# Sheet2.net
KiCad netlist of a schematic drawn in Altium Designer
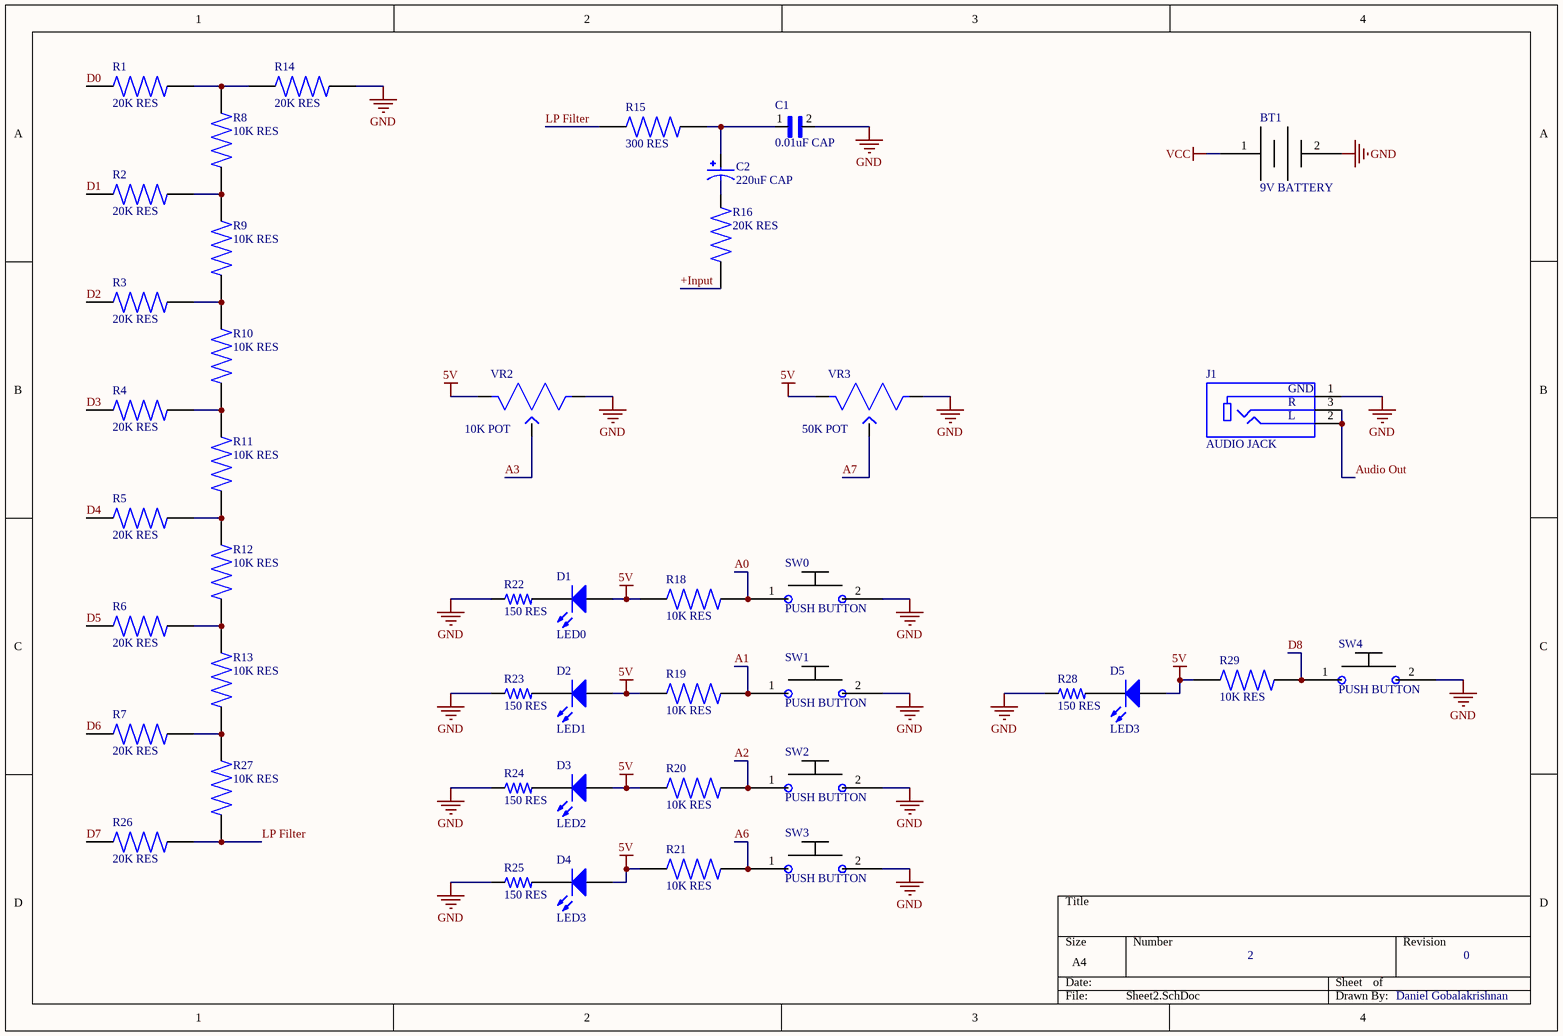
[diagram p0: Sheet2.SchDoc]

(export (version "E")
  (design (tool "Eeschema 10.0.6"))
  (components
    (comp (ref "BT1")
      (value "9V BATTERY")
      (footprint "9V Battery")
      (libsource (lib "Library") (part "9V BATTERY"))
    )
    (comp (ref "C1")
      (value "0.01uF CAP")
      (footprint "10uF CAP")
      (description "Lead Capacitor E(JIS) with Capacitance: 1000pF and Rated Voltage: 400Vac(r.m.s.)")
      (fields (field (name "DIGI-KEY_PART_NUMBER") "490-16237-1-ND") (field (name "MP") "DE2E3SA102MN3AY02F"))
      (libsource (lib "Library") (part "0.01uF CAP"))
    )
    (comp (ref "C2")
      (value "220uF CAP")
      (footprint "220uF CAP")
      (description "33ÂµF 250V Aluminum Electrolytic Capacitors Radial, Can 5000 Hrs @ 105Â°C")
      (fields (field (name "MP") "UPM2E330MHD1TN") (field (name "MF") "Nichicon"))
      (libsource (lib "Library") (part "220uF CAP"))
    )
    (comp (ref "D1")
      (value "LED0")
      (footprint "LED-1")
      (description "Typical RED GaAs LED")
      (fields (field (name "PUBLISHER") "Altium Limited"))
      (libsource (lib "Miscellaneous Devices") (part "LED1"))
    )
    (comp (ref "D2")
      (value "LED1")
      (footprint "LED-1")
      (description "Typical RED GaAs LED")
      (fields (field (name "PUBLISHER") "Altium Limited"))
      (libsource (lib "Miscellaneous Devices") (part "LED1"))
    )
    (comp (ref "D3")
      (value "LED2")
      (footprint "LED-1")
      (description "Typical RED GaAs LED")
      (fields (field (name "PUBLISHER") "Altium Limited"))
      (libsource (lib "Miscellaneous Devices") (part "LED1"))
    )
    (comp (ref "D4")
      (value "LED3")
      (footprint "LED-1")
      (description "Typical RED GaAs LED")
      (fields (field (name "PUBLISHER") "Altium Limited"))
      (libsource (lib "Miscellaneous Devices") (part "LED1"))
    )
    (comp (ref "D5")
      (value "LED3")
      (footprint "LED-1")
      (description "Typical RED GaAs LED")
      (fields (field (name "PUBLISHER") "Altium Limited"))
      (libsource (lib "Miscellaneous Devices") (part "LED1"))
    )
    (comp (ref "J1")
      (value "AUDIO JACK")
      (footprint "AUDIO JACK")
      (description "3.5 mm, Stereo, Right Angle, Through Hole, Audio Jack Connector")
      (fields (field (name "MF") "CUI Devices") (field (name "MP") "SJ1-3533N"))
      (libsource (lib "Library") (part "AUDIO JACK"))
    )
    (comp (ref "R1")
      (value "20K RES")
      (footprint "20K RES")
      (fields (field (name "MP") "RMCF1206JT20K0"))
      (libsource (lib "Library") (part "20K RES"))
    )
    (comp (ref "R2")
      (value "20K RES")
      (footprint "20K RES")
      (fields (field (name "MP") "RMCF1206JT20K0"))
      (libsource (lib "Library") (part "20K RES"))
    )
    (comp (ref "R3")
      (value "20K RES")
      (footprint "20K RES")
      (fields (field (name "MP") "RMCF1206JT20K0"))
      (libsource (lib "Library") (part "20K RES"))
    )
    (comp (ref "R4")
      (value "20K RES")
      (footprint "20K RES")
      (fields (field (name "MP") "RMCF1206JT20K0"))
      (libsource (lib "Library") (part "20K RES"))
    )
    (comp (ref "R5")
      (value "20K RES")
      (footprint "20K RES")
      (fields (field (name "MP") "RMCF1206JT20K0"))
      (libsource (lib "Library") (part "20K RES"))
    )
    (comp (ref "R6")
      (value "20K RES")
      (footprint "20K RES")
      (fields (field (name "MP") "RMCF1206JT20K0"))
      (libsource (lib "Library") (part "20K RES"))
    )
    (comp (ref "R7")
      (value "20K RES")
      (footprint "20K RES")
      (fields (field (name "MP") "RMCF1206JT20K0"))
      (libsource (lib "Library") (part "20K RES"))
    )
    (comp (ref "R8")
      (value "10K RES")
      (footprint "10K RES")
      (description "10 kOhms Â±1% 0.25W, 1/4W Chip Resistor 1206 (3216 Metric) Automotive AEC-Q200 Thick Film")
      (fields (field (name "MP") "RMCF1206FT10K0") (field (name "MF") "Stackpole Electronics Inc"))
      (libsource (lib "Library") (part "10K RES"))
    )
    (comp (ref "R9")
      (value "10K RES")
      (footprint "10K RES")
      (description "10 kOhms Â±1% 0.25W, 1/4W Chip Resistor 1206 (3216 Metric) Automotive AEC-Q200 Thick Film")
      (fields (field (name "MP") "RMCF1206FT10K0") (field (name "MF") "Stackpole Electronics Inc"))
      (libsource (lib "Library") (part "10K RES"))
    )
    (comp (ref "R10")
      (value "10K RES")
      (footprint "10K RES")
      (description "10 kOhms Â±1% 0.25W, 1/4W Chip Resistor 1206 (3216 Metric) Automotive AEC-Q200 Thick Film")
      (fields (field (name "MP") "RMCF1206FT10K0") (field (name "MF") "Stackpole Electronics Inc"))
      (libsource (lib "Library") (part "10K RES"))
    )
    (comp (ref "R11")
      (value "10K RES")
      (footprint "10K RES")
      (description "10 kOhms Â±1% 0.25W, 1/4W Chip Resistor 1206 (3216 Metric) Automotive AEC-Q200 Thick Film")
      (fields (field (name "MP") "RMCF1206FT10K0") (field (name "MF") "Stackpole Electronics Inc"))
      (libsource (lib "Library") (part "10K RES"))
    )
    (comp (ref "R12")
      (value "10K RES")
      (footprint "10K RES")
      (description "10 kOhms Â±1% 0.25W, 1/4W Chip Resistor 1206 (3216 Metric) Automotive AEC-Q200 Thick Film")
      (fields (field (name "MP") "RMCF1206FT10K0") (field (name "MF") "Stackpole Electronics Inc"))
      (libsource (lib "Library") (part "10K RES"))
    )
    (comp (ref "R13")
      (value "10K RES")
      (footprint "10K RES")
      (description "10 kOhms Â±1% 0.25W, 1/4W Chip Resistor 1206 (3216 Metric) Automotive AEC-Q200 Thick Film")
      (fields (field (name "MP") "RMCF1206FT10K0") (field (name "MF") "Stackpole Electronics Inc"))
      (libsource (lib "Library") (part "10K RES"))
    )
    (comp (ref "R14")
      (value "20K RES")
      (footprint "20K RES")
      (fields (field (name "MP") "RMCF1206JT20K0"))
      (libsource (lib "Library") (part "20K RES"))
    )
    (comp (ref "R15")
      (value "300 RES")
      (footprint "300 RES")
      (description "CRCW Series 1206 0.25 W 300 Ohm Â±5 % Â±200 ppm/K SMT Thick Film Chip Resistor")
      (fields (field (name "MP") "CRCW1206300RJNEA"))
      (libsource (lib "Library") (part "300 RES"))
    )
    (comp (ref "R16")
      (value "20K RES")
      (footprint "20K RES")
      (fields (field (name "MP") "RMCF1206JT20K0"))
      (libsource (lib "Library") (part "20K RES"))
    )
    (comp (ref "R18")
      (value "10K RES")
      (footprint "10K RES")
      (description "10 kOhms Â±1% 0.25W, 1/4W Chip Resistor 1206 (3216 Metric) Automotive AEC-Q200 Thick Film")
      (fields (field (name "MP") "RMCF1206FT10K0") (field (name "MF") "Stackpole Electronics Inc"))
      (libsource (lib "Library") (part "10K RES"))
    )
    (comp (ref "R19")
      (value "10K RES")
      (footprint "10K RES")
      (description "10 kOhms Â±1% 0.25W, 1/4W Chip Resistor 1206 (3216 Metric) Automotive AEC-Q200 Thick Film")
      (fields (field (name "MP") "RMCF1206FT10K0") (field (name "MF") "Stackpole Electronics Inc"))
      (libsource (lib "Library") (part "10K RES"))
    )
    (comp (ref "R20")
      (value "10K RES")
      (footprint "10K RES")
      (description "10 kOhms Â±1% 0.25W, 1/4W Chip Resistor 1206 (3216 Metric) Automotive AEC-Q200 Thick Film")
      (fields (field (name "MP") "RMCF1206FT10K0") (field (name "MF") "Stackpole Electronics Inc"))
      (libsource (lib "Library") (part "10K RES"))
    )
    (comp (ref "R21")
      (value "10K RES")
      (footprint "10K RES")
      (description "10 kOhms Â±1% 0.25W, 1/4W Chip Resistor 1206 (3216 Metric) Automotive AEC-Q200 Thick Film")
      (fields (field (name "MP") "RMCF1206FT10K0") (field (name "MF") "Stackpole Electronics Inc"))
      (libsource (lib "Library") (part "10K RES"))
    )
    (comp (ref "R22")
      (value "150 RES")
      (footprint "150 RES")
      (description "Through Hole Carbon Film Resistor, Cfr Series, 150 Ohm, 500 Mw, - 5%, 350 V, Axial Leaded")
      (fields (field (name "MF") "TE Connectivity") (field (name "MP") "CFR50J150R"))
      (libsource (lib "Library") (part "150 RES"))
    )
    (comp (ref "R23")
      (value "150 RES")
      (footprint "150 RES")
      (description "Through Hole Carbon Film Resistor, Cfr Series, 150 Ohm, 500 Mw, - 5%, 350 V, Axial Leaded")
      (fields (field (name "MF") "TE Connectivity") (field (name "MP") "CFR50J150R"))
      (libsource (lib "Library") (part "150 RES"))
    )
    (comp (ref "R24")
      (value "150 RES")
      (footprint "150 RES")
      (description "Through Hole Carbon Film Resistor, Cfr Series, 150 Ohm, 500 Mw, - 5%, 350 V, Axial Leaded")
      (fields (field (name "MF") "TE Connectivity") (field (name "MP") "CFR50J150R"))
      (libsource (lib "Library") (part "150 RES"))
    )
    (comp (ref "R25")
      (value "150 RES")
      (footprint "150 RES")
      (description "Through Hole Carbon Film Resistor, Cfr Series, 150 Ohm, 500 Mw, - 5%, 350 V, Axial Leaded")
      (fields (field (name "MF") "TE Connectivity") (field (name "MP") "CFR50J150R"))
      (libsource (lib "Library") (part "150 RES"))
    )
    (comp (ref "R26")
      (value "20K RES")
      (footprint "20K RES")
      (fields (field (name "MP") "RMCF1206JT20K0"))
      (libsource (lib "Library") (part "20K RES"))
    )
    (comp (ref "R27")
      (value "10K RES")
      (footprint "10K RES")
      (description "10 kOhms Â±1% 0.25W, 1/4W Chip Resistor 1206 (3216 Metric) Automotive AEC-Q200 Thick Film")
      (fields (field (name "MP") "RMCF1206FT10K0") (field (name "MF") "Stackpole Electronics Inc"))
      (libsource (lib "Library") (part "10K RES"))
    )
    (comp (ref "R28")
      (value "150 RES")
      (footprint "150 RES")
      (description "Through Hole Carbon Film Resistor, Cfr Series, 150 Ohm, 500 Mw, - 5%, 350 V, Axial Leaded")
      (fields (field (name "MF") "TE Connectivity") (field (name "MP") "CFR50J150R"))
      (libsource (lib "Library") (part "150 RES"))
    )
    (comp (ref "R29")
      (value "10K RES")
      (footprint "10K RES")
      (description "10 kOhms Â±1% 0.25W, 1/4W Chip Resistor 1206 (3216 Metric) Automotive AEC-Q200 Thick Film")
      (fields (field (name "MP") "RMCF1206FT10K0") (field (name "MF") "Stackpole Electronics Inc"))
      (libsource (lib "Library") (part "10K RES"))
    )
    (comp (ref "SW0")
      (value "PUSH BUTTON")
      (footprint "Push Button")
      (description "Push Button")
      (libsource (lib "Library") (part "PUSH BUTTON"))
    )
    (comp (ref "SW1")
      (value "PUSH BUTTON")
      (footprint "Push Button")
      (description "Push Button")
      (libsource (lib "Library") (part "PUSH BUTTON"))
    )
    (comp (ref "SW2")
      (value "PUSH BUTTON")
      (footprint "Push Button")
      (description "Push Button")
      (libsource (lib "Library") (part "PUSH BUTTON"))
    )
    (comp (ref "SW3")
      (value "PUSH BUTTON")
      (footprint "Push Button")
      (description "Push Button")
      (libsource (lib "Library") (part "PUSH BUTTON"))
    )
    (comp (ref "SW4")
      (value "PUSH BUTTON")
      (footprint "Push Button")
      (description "Push Button")
      (libsource (lib "Library") (part "PUSH BUTTON"))
    )
    (comp (ref "VR2")
      (value "10K POT")
      (footprint "10K POT")
      (description "POT 10K OHM 1/10W PLASTIC LOG")
      (fields (field (name "MF") "TT Electronics/BI") (field (name "DIGI-KEY_PART_NUMBER") "987-1304-ND"))
      (libsource (lib "Library") (part "10K POT"))
    )
    (comp (ref "VR3")
      (value "50K POT")
      (footprint "50K POT")
      (description "POT 50K OHM 1/5W PLASTIC LINEAR")
      (fields (field (name "MF") "TT Electronics/BI") (field (name "DIGI-KEY_PART_NUMBER") "987-1304-ND"))
      (libsource (lib "Library") (part "50K POT"))
    )
  )
  (nets
    (net (code "1") (name "/+Input") (class "Default")
      (node (ref "R16") (pin "2") (pinfunction "2_2") (pintype "passive"))
    )
    (net (code "2") (name "/A0") (class "Default")
      (node (ref "R18") (pin "1") (pinfunction "1_1") (pintype "passive"))
      (node (ref "SW0") (pin "1") (pintype "passive"))
    )
    (net (code "3") (name "/A1") (class "Default")
      (node (ref "R19") (pin "1") (pinfunction "1_1") (pintype "passive"))
      (node (ref "SW1") (pin "1") (pintype "passive"))
    )
    (net (code "4") (name "/A2") (class "Default")
      (node (ref "R20") (pin "1") (pinfunction "1_1") (pintype "passive"))
      (node (ref "SW2") (pin "1") (pintype "passive"))
    )
    (net (code "5") (name "/A3") (class "Default")
      (node (ref "VR2") (pin "2") (pinfunction "2_2") (pintype "bidirectional"))
    )
    (net (code "6") (name "/A6") (class "Default")
      (node (ref "R21") (pin "1") (pinfunction "1_1") (pintype "passive"))
      (node (ref "SW3") (pin "1") (pintype "passive"))
    )
    (net (code "7") (name "/A7") (class "Default")
      (node (ref "VR3") (pin "2") (pinfunction "2_2") (pintype "bidirectional"))
    )
    (net (code "8") (name "/Audio Out") (class "Default")
      (node (ref "J1") (pin "2") (pinfunction "2_2") (pintype "passive"))
      (node (ref "J1") (pin "3") (pinfunction "3_3") (pintype "passive"))
    )
    (net (code "9") (name "/D0") (class "Default")
      (node (ref "R1") (pin "1") (pinfunction "1_1") (pintype "passive"))
    )
    (net (code "10") (name "/D1") (class "Default")
      (node (ref "R2") (pin "1") (pinfunction "1_1") (pintype "passive"))
    )
    (net (code "11") (name "/D2") (class "Default")
      (node (ref "R3") (pin "1") (pinfunction "1_1") (pintype "passive"))
    )
    (net (code "12") (name "/D3") (class "Default")
      (node (ref "R4") (pin "1") (pinfunction "1_1") (pintype "passive"))
    )
    (net (code "13") (name "/D4") (class "Default")
      (node (ref "R5") (pin "1") (pinfunction "1_1") (pintype "passive"))
    )
    (net (code "14") (name "/D5") (class "Default")
      (node (ref "R6") (pin "1") (pinfunction "1_1") (pintype "passive"))
    )
    (net (code "15") (name "/D6") (class "Default")
      (node (ref "R7") (pin "1") (pinfunction "1_1") (pintype "passive"))
    )
    (net (code "16") (name "/D7") (class "Default")
      (node (ref "R26") (pin "1") (pinfunction "1_1") (pintype "passive"))
    )
    (net (code "17") (name "/D8") (class "Default")
      (node (ref "R29") (pin "1") (pinfunction "1_1") (pintype "passive"))
      (node (ref "SW4") (pin "1") (pintype "passive"))
    )
    (net (code "18") (name "/LP Filter") (class "Default")
      (node (ref "R15") (pin "1") (pinfunction "1_1") (pintype "passive"))
      (node (ref "R26") (pin "2") (pinfunction "2_2") (pintype "passive"))
      (node (ref "R27") (pin "1") (pinfunction "1_1") (pintype "passive"))
    )
    (net (code "19") (name "5V") (class "Default")
      (node (ref "D1") (pin "1") (pinfunction "A_1") (pintype "passive"))
      (node (ref "D2") (pin "1") (pinfunction "A_1") (pintype "passive"))
      (node (ref "D3") (pin "1") (pinfunction "A_1") (pintype "passive"))
      (node (ref "D4") (pin "1") (pinfunction "A_1") (pintype "passive"))
      (node (ref "D5") (pin "1") (pinfunction "A_1") (pintype "passive"))
      (node (ref "R18") (pin "2") (pinfunction "2_2") (pintype "passive"))
      (node (ref "R19") (pin "2") (pinfunction "2_2") (pintype "passive"))
      (node (ref "R20") (pin "2") (pinfunction "2_2") (pintype "passive"))
      (node (ref "R21") (pin "2") (pinfunction "2_2") (pintype "passive"))
      (node (ref "R29") (pin "2") (pinfunction "2_2") (pintype "passive"))
      (node (ref "VR2") (pin "1") (pinfunction "1_1") (pintype "bidirectional"))
      (node (ref "VR3") (pin "1") (pinfunction "1_1") (pintype "bidirectional"))
    )
    (net (code "20") (name "GND") (class "Default")
      (node (ref "BT1") (pin "2") (pintype "passive"))
      (node (ref "C1") (pin "2") (pinfunction "2_2") (pintype "passive"))
      (node (ref "J1") (pin "1") (pinfunction "1_1") (pintype "passive"))
      (node (ref "R14") (pin "2") (pinfunction "2_2") (pintype "passive"))
      (node (ref "R22") (pin "1") (pinfunction "1_1") (pintype "passive"))
      (node (ref "R23") (pin "1") (pinfunction "1_1") (pintype "passive"))
      (node (ref "R24") (pin "1") (pinfunction "1_1") (pintype "passive"))
      (node (ref "R25") (pin "1") (pinfunction "1_1") (pintype "passive"))
      (node (ref "R28") (pin "1") (pinfunction "1_1") (pintype "passive"))
      (node (ref "SW0") (pin "2") (pintype "passive"))
      (node (ref "SW1") (pin "2") (pintype "passive"))
      (node (ref "SW2") (pin "2") (pintype "passive"))
      (node (ref "SW3") (pin "2") (pintype "passive"))
      (node (ref "SW4") (pin "2") (pintype "passive"))
      (node (ref "VR2") (pin "3") (pinfunction "3_3") (pintype "bidirectional"))
      (node (ref "VR3") (pin "3") (pinfunction "3_3") (pintype "bidirectional"))
    )
    (net (code "21") (name "Net-(C1-Pad1)") (class "Default")
      (node (ref "C1") (pin "1") (pinfunction "1_1") (pintype "passive"))
      (node (ref "C2") (pin "P") (pinfunction "P_P") (pintype "passive"))
      (node (ref "R15") (pin "2") (pinfunction "2_2") (pintype "passive"))
    )
    (net (code "22") (name "Net-(C2-PadN)") (class "Default")
      (node (ref "C2") (pin "N") (pinfunction "N_N") (pintype "passive"))
      (node (ref "R16") (pin "1") (pinfunction "1_1") (pintype "passive"))
    )
    (net (code "23") (name "Net-(D1-K)") (class "Default")
      (node (ref "D1") (pin "2") (pinfunction "K_2") (pintype "passive"))
      (node (ref "R22") (pin "2") (pinfunction "2_2") (pintype "passive"))
    )
    (net (code "24") (name "Net-(D2-K)") (class "Default")
      (node (ref "D2") (pin "2") (pinfunction "K_2") (pintype "passive"))
      (node (ref "R23") (pin "2") (pinfunction "2_2") (pintype "passive"))
    )
    (net (code "25") (name "Net-(D3-K)") (class "Default")
      (node (ref "D3") (pin "2") (pinfunction "K_2") (pintype "passive"))
      (node (ref "R24") (pin "2") (pinfunction "2_2") (pintype "passive"))
    )
    (net (code "26") (name "Net-(D4-K)") (class "Default")
      (node (ref "D4") (pin "2") (pinfunction "K_2") (pintype "passive"))
      (node (ref "R25") (pin "2") (pinfunction "2_2") (pintype "passive"))
    )
    (net (code "27") (name "Net-(D5-K)") (class "Default")
      (node (ref "D5") (pin "2") (pinfunction "K_2") (pintype "passive"))
      (node (ref "R28") (pin "2") (pinfunction "2_2") (pintype "passive"))
    )
    (net (code "28") (name "Net-(R1-Pad2)") (class "Default")
      (node (ref "R1") (pin "2") (pinfunction "2_2") (pintype "passive"))
      (node (ref "R14") (pin "1") (pinfunction "1_1") (pintype "passive"))
      (node (ref "R8") (pin "2") (pinfunction "2_2") (pintype "passive"))
    )
    (net (code "29") (name "Net-(R2-Pad2)") (class "Default")
      (node (ref "R2") (pin "2") (pinfunction "2_2") (pintype "passive"))
      (node (ref "R8") (pin "1") (pinfunction "1_1") (pintype "passive"))
      (node (ref "R9") (pin "2") (pinfunction "2_2") (pintype "passive"))
    )
    (net (code "30") (name "Net-(R10-Pad1)") (class "Default")
      (node (ref "R10") (pin "1") (pinfunction "1_1") (pintype "passive"))
      (node (ref "R11") (pin "2") (pinfunction "2_2") (pintype "passive"))
      (node (ref "R4") (pin "2") (pinfunction "2_2") (pintype "passive"))
    )
    (net (code "31") (name "Net-(R10-Pad2)") (class "Default")
      (node (ref "R10") (pin "2") (pinfunction "2_2") (pintype "passive"))
      (node (ref "R3") (pin "2") (pinfunction "2_2") (pintype "passive"))
      (node (ref "R9") (pin "1") (pinfunction "1_1") (pintype "passive"))
    )
    (net (code "32") (name "Net-(R11-Pad1)") (class "Default")
      (node (ref "R11") (pin "1") (pinfunction "1_1") (pintype "passive"))
      (node (ref "R12") (pin "2") (pinfunction "2_2") (pintype "passive"))
      (node (ref "R5") (pin "2") (pinfunction "2_2") (pintype "passive"))
    )
    (net (code "33") (name "Net-(R12-Pad1)") (class "Default")
      (node (ref "R12") (pin "1") (pinfunction "1_1") (pintype "passive"))
      (node (ref "R13") (pin "2") (pinfunction "2_2") (pintype "passive"))
      (node (ref "R6") (pin "2") (pinfunction "2_2") (pintype "passive"))
    )
    (net (code "34") (name "Net-(R13-Pad1)") (class "Default")
      (node (ref "R13") (pin "1") (pinfunction "1_1") (pintype "passive"))
      (node (ref "R27") (pin "2") (pinfunction "2_2") (pintype "passive"))
      (node (ref "R7") (pin "2") (pinfunction "2_2") (pintype "passive"))
    )
    (net (code "35") (name "VCC") (class "Default") (node (ref "BT1") (pin "1") (pintype "passive")))
  )
)
